# Current_Controller_LM258.net
KiCad netlist of a schematic drawn in Altium Designer
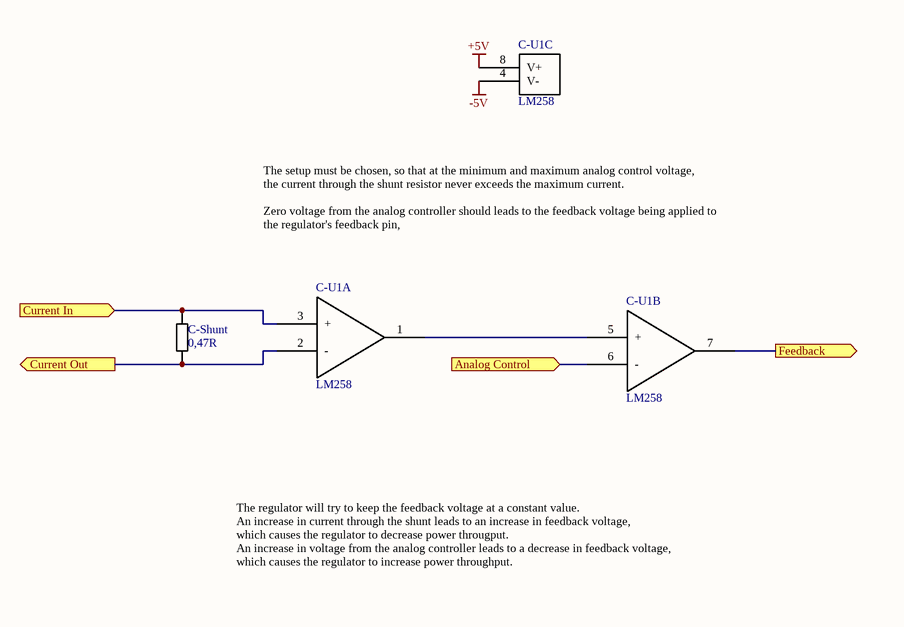
[diagram p0: Current Controller LM258.SchDoc]

(export (version "E")
  (design (tool "Eeschema 10.0.6"))
  (components
    (comp (ref "C-Shunt")
      (value "0,47R")
      (footprint "R 0805 / 2012")
      (libsource (lib "Standard") (part "Resistor"))
    )
    (comp (ref "C-U1")
      (value "LM258")
      (footprint "SOIC-8")
      (description "Dual OpAmp")
      (libsource (lib "ICs") (part "LM258"))
    )
  )
  (nets
    (net (code "1") (name "+5V") (class "Default")
      (node (ref "C-U1") (pin "8") (pinfunction "V+_8") (pintype "passive"))
    )
    (net (code "2") (name "-5V") (class "Default")
      (node (ref "C-U1") (pin "4") (pinfunction "V-_4") (pintype "passive"))
    )
    (net (code "3") (name "/Analog Control") (class "Default")
      (node (ref "C-U1") (pin "6") (pinfunction "-_6") (pintype "passive"))
    )
    (net (code "4") (name "/Current In") (class "Default")
      (node (ref "C-Shunt") (pin "2") (pinfunction "2_2") (pintype "passive"))
      (node (ref "C-U1") (pin "3") (pinfunction "+_3") (pintype "passive"))
    )
    (net (code "5") (name "/Current Out") (class "Default")
      (node (ref "C-Shunt") (pin "1") (pinfunction "1_1") (pintype "passive"))
      (node (ref "C-U1") (pin "2") (pinfunction "-_2") (pintype "passive"))
    )
    (net (code "6") (name "/Feedback") (class "Default")
      (node (ref "C-U1") (pin "7") (pinfunction "OUT_7") (pintype "passive"))
    )
    (net (code "7") (name "Net-(C-U1A-OUT)") (class "Default")
      (node (ref "C-U1") (pin "1") (pinfunction "OUT_1") (pintype "passive"))
      (node (ref "C-U1") (pin "5") (pinfunction "+_5") (pintype "passive"))
    )
  )
)
